# SPI_Bus_Transceiver.net
KiCad netlist of a schematic drawn in Altium Designer
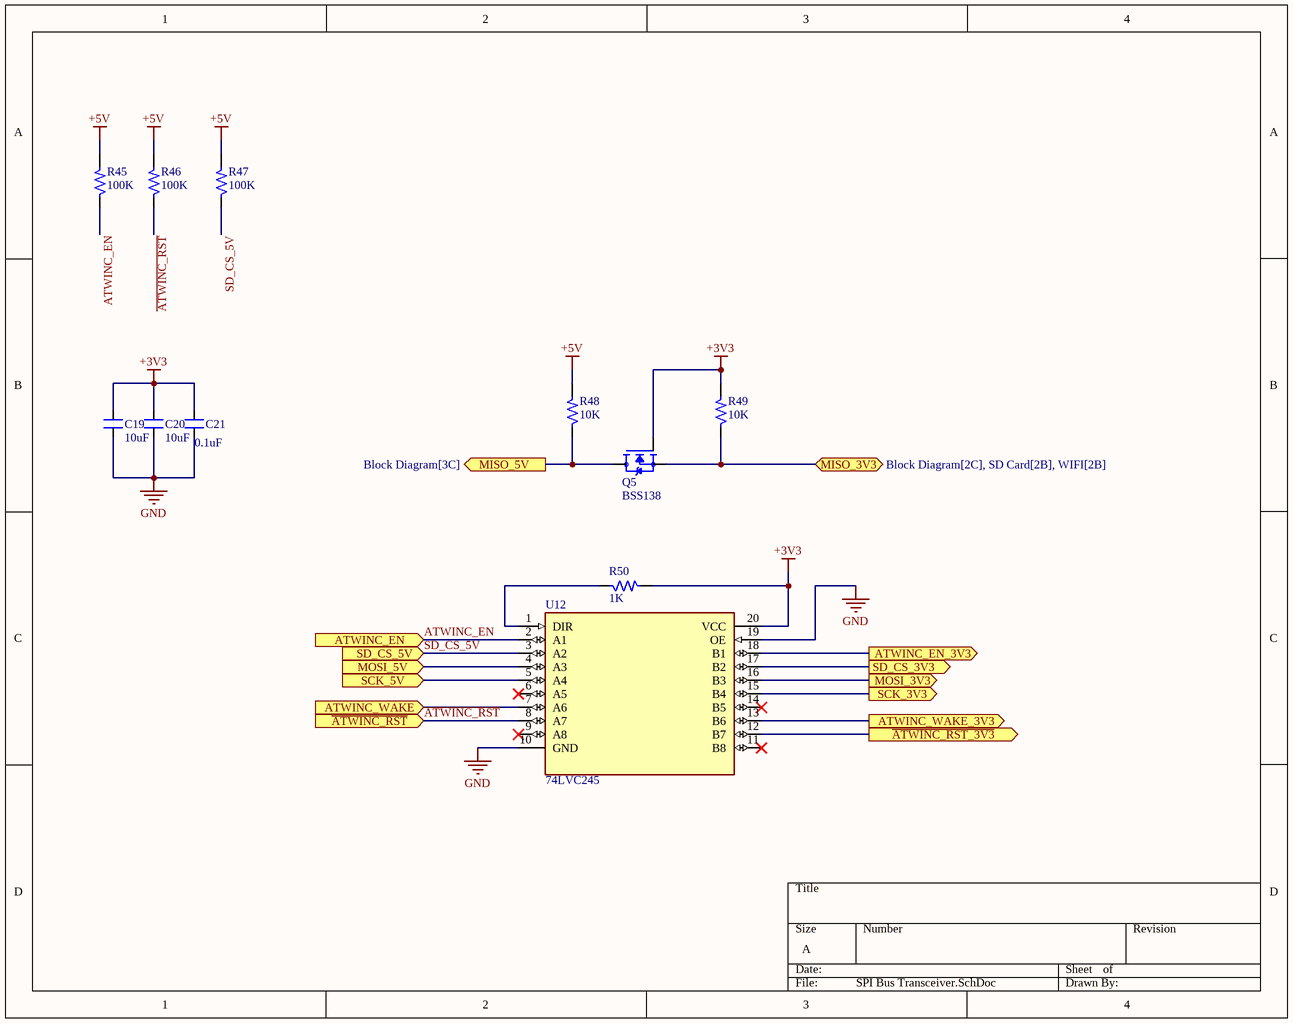
[diagram p0: SPI Bus Transceiver.SchDoc]

(export (version "E")
  (design (tool "Eeschema 10.0.6"))
  (components
    (comp (ref "C19")
      (value "10uF")
      (footprint "CAP_1206")
      (description "10µF ±10% 50V Ceramic Capacitor X7R 1206 (3216 Metric)")
      (fields
        (field (name "MANUFACTURER") "KEMET")
        (field (name "MANUFACTURER PART NUMBER") "CL31B106KBHNNNE")
      )
      (libsource (lib "ESTEEMPCBLIB") (part "CAP_10uF-50V-10%-1206"))
    )
    (comp (ref "C20")
      (value "10uF")
      (footprint "CAP_1206")
      (description "10µF ±10% 50V Ceramic Capacitor X7R 1206 (3216 Metric)")
      (fields
        (field (name "MANUFACTURER") "KEMET")
        (field (name "MANUFACTURER PART NUMBER") "CL31B106KBHNNNE")
      )
      (libsource (lib "ESTEEMPCBLIB") (part "CAP_10uF-50V-10%-1206"))
    )
    (comp (ref "C21")
      (value "0.1uF")
      (footprint "CAP_0805")
      (description "0.1µF ±5% 50V Ceramic Capacitor X7R 0805 (2012 Metric)")
      (fields
        (field (name "MANUFACTURER") "AVX Corporation")
        (field (name "MANUFACTURER PART NUMBER") "08055C104JAT4A")
      )
      (libsource (lib "ESTEEMPCBLIB") (part "CAP_0.1uF-50V-5%-0805"))
    )
    (comp (ref "Q5")
      (value "BSS138")
      (footprint "SOT95P240X111-3N")
      (description "N-Channel 50V 220mA (Ta) 360mW (Ta) Surface Mount SOT-23-3")
      (libsource (lib "TAREKPCBLIB") (part "BSS138"))
    )
    (comp (ref "R45")
      (value "100K")
      (footprint "RES_0805")
      (description "100 kOhms ±1% 0.125W, 1/8W Chip Resistor 0805 (2012 Metric) Automotive AEC-Q200 Thick Film")
      (fields (field (name "MANUFACTURER") "Walsin") (field (name "MANUFACTURER PART NUMBER") "WR08X1003FTL"))
      (libsource (lib "ESTEEMPCBLIB") (part "RES_100K-0.125W-1%-0805"))
    )
    (comp (ref "R46")
      (value "100K")
      (footprint "RES_0805")
      (description "100 kOhms ±1% 0.125W, 1/8W Chip Resistor 0805 (2012 Metric) Automotive AEC-Q200 Thick Film")
      (fields (field (name "MANUFACTURER") "Walsin") (field (name "MANUFACTURER PART NUMBER") "WR08X1003FTL"))
      (libsource (lib "ESTEEMPCBLIB") (part "RES_100K-0.125W-1%-0805"))
    )
    (comp (ref "R47")
      (value "100K")
      (footprint "RES_0805")
      (description "100 kOhms ±1% 0.125W, 1/8W Chip Resistor 0805 (2012 Metric) Automotive AEC-Q200 Thick Film")
      (fields (field (name "MANUFACTURER") "Walsin") (field (name "MANUFACTURER PART NUMBER") "WR08X1003FTL"))
      (libsource (lib "ESTEEMPCBLIB") (part "RES_100K-0.125W-1%-0805"))
    )
    (comp (ref "R48")
      (value "10K")
      (footprint "RES_0805")
      (description "10 kOhms ±1% 0.125W, 1/8W Chip Resistor 0805 (2012 Metric) Automotive AEC-Q200 Thick Film")
      (fields (field (name "MANUFACTURER") "CTS") (field (name "MANUFACTURER PART NUMBER") "WR08X1002FTL"))
      (libsource (lib "ESTEEMPCBLIB") (part "RES_10K-0.125W-1%-0805"))
    )
    (comp (ref "R49")
      (value "10K")
      (footprint "RES_0805")
      (description "10 kOhms ±1% 0.125W, 1/8W Chip Resistor 0805 (2012 Metric) Automotive AEC-Q200 Thick Film")
      (fields (field (name "MANUFACTURER") "CTS") (field (name "MANUFACTURER PART NUMBER") "WR08X1002FTL"))
      (libsource (lib "ESTEEMPCBLIB") (part "RES_10K-0.125W-1%-0805"))
    )
    (comp (ref "R50")
      (value "1K")
      (footprint "RES_0805")
      (description "1 kOhms ±1% 0.125W, 1/8W Chip Resistor 0805 (2012 Metric) Moisture Resistant Thick Film")
      (fields (field (name "MANUFACTURER") "Walsin") (field (name "MANUFACTURER PART NUMBER") "WR08X1001FTL"))
      (libsource (lib "ESTEEMPCBLIB") (part "RES_1K-0.125W-1%-0805"))
    )
    (comp (ref "U12")
      (value "74LVC245")
      (footprint "SOIC-20-W")
      (description "Transceiver, Non-Inverting 1 Element 8 Bit per Element 3-State Output 20-TSSOP")
      (fields (field (name "MF") "ON Semiconductor"))
      (libsource (lib "TAREKPCBLIB") (part "74LVC245"))
    )
  )
  (nets
    (net (code "1") (name "+3V3") (class "Default")
      (node (ref "C19") (pin "2") (pinfunction "2_2") (pintype "passive"))
      (node (ref "C20") (pin "2") (pinfunction "2_2") (pintype "passive"))
      (node (ref "C21") (pin "2") (pinfunction "2_2") (pintype "passive"))
      (node (ref "Q5") (pin "1") (pinfunction "G_1") (pintype "passive"))
      (node (ref "R49") (pin "2") (pinfunction "2_2") (pintype "passive"))
      (node (ref "R50") (pin "2") (pinfunction "2_2") (pintype "passive"))
      (node (ref "U12") (pin "20") (pinfunction "VCC_20") (pintype "power_in"))
    )
    (net (code "2") (name "+5V") (class "Default")
      (node (ref "R45") (pin "2") (pinfunction "2_2") (pintype "passive"))
      (node (ref "R46") (pin "2") (pinfunction "2_2") (pintype "passive"))
      (node (ref "R47") (pin "2") (pinfunction "2_2") (pintype "passive"))
      (node (ref "R48") (pin "2") (pinfunction "2_2") (pintype "passive"))
    )
    (net (code "3") (name "/ATWINC_EN") (class "Default")
      (node (ref "R45") (pin "1") (pinfunction "1_1") (pintype "passive"))
      (node (ref "U12") (pin "2") (pinfunction "A1_2") (pintype "bidirectional"))
    )
    (net (code "4") (name "/ATWINC_EN_3V3") (class "Default")
      (node (ref "U12") (pin "18") (pinfunction "B1_18") (pintype "bidirectional"))
    )
    (net (code "5") (name "/ATWINC_RST") (class "Default")
      (node (ref "R46") (pin "1") (pinfunction "1_1") (pintype "passive"))
      (node (ref "U12") (pin "8") (pinfunction "A7_8") (pintype "bidirectional"))
    )
    (net (code "6") (name "/ATWINC_RST_3V3") (class "Default")
      (node (ref "U12") (pin "12") (pinfunction "B7_12") (pintype "bidirectional"))
    )
    (net (code "7") (name "/ATWINC_WAKE") (class "Default")
      (node (ref "U12") (pin "7") (pinfunction "A6_7") (pintype "bidirectional"))
    )
    (net (code "8") (name "/ATWINC_WAKE_3V3") (class "Default")
      (node (ref "U12") (pin "13") (pinfunction "B6_13") (pintype "bidirectional"))
    )
    (net (code "9") (name "/MISO_3V3") (class "Default")
      (node (ref "Q5") (pin "2") (pinfunction "S_2") (pintype "passive"))
      (node (ref "R49") (pin "1") (pinfunction "1_1") (pintype "passive"))
    )
    (net (code "10") (name "/MISO_5V") (class "Default")
      (node (ref "Q5") (pin "3") (pinfunction "D_3") (pintype "passive"))
      (node (ref "R48") (pin "1") (pinfunction "1_1") (pintype "passive"))
    )
    (net (code "11") (name "/MOSI_3V3") (class "Default")
      (node (ref "U12") (pin "16") (pinfunction "B3_16") (pintype "bidirectional"))
    )
    (net (code "12") (name "/MOSI_5V") (class "Default")
      (node (ref "U12") (pin "4") (pinfunction "A3_4") (pintype "bidirectional"))
    )
    (net (code "13") (name "/SCK_3V3") (class "Default")
      (node (ref "U12") (pin "15") (pinfunction "B4_15") (pintype "bidirectional"))
    )
    (net (code "14") (name "/SCK_5V") (class "Default")
      (node (ref "U12") (pin "5") (pinfunction "A4_5") (pintype "bidirectional"))
    )
    (net (code "15") (name "/SD_CS_3V3") (class "Default")
      (node (ref "U12") (pin "17") (pinfunction "B2_17") (pintype "bidirectional"))
    )
    (net (code "16") (name "/SD_CS_5V") (class "Default")
      (node (ref "R47") (pin "1") (pinfunction "1_1") (pintype "passive"))
      (node (ref "U12") (pin "3") (pinfunction "A2_3") (pintype "bidirectional"))
    )
    (net (code "17") (name "GND") (class "Default")
      (node (ref "C19") (pin "1") (pinfunction "1_1") (pintype "passive"))
      (node (ref "C20") (pin "1") (pinfunction "1_1") (pintype "passive"))
      (node (ref "C21") (pin "1") (pinfunction "1_1") (pintype "passive"))
      (node (ref "U12") (pin "10") (pinfunction "GND_10") (pintype "power_in"))
      (node (ref "U12") (pin "19") (pinfunction "OE_19") (pintype "input"))
    )
    (net (code "18") (name "Net-(U12-DIR)") (class "Default")
      (node (ref "R50") (pin "1") (pinfunction "1_1") (pintype "passive"))
      (node (ref "U12") (pin "1") (pinfunction "DIR_1") (pintype "input"))
    )
    (net (code "19") (name "unconnected-(U12-A5-Pad6)") (class "Default")
      (node (ref "U12") (pin "6") (pinfunction "A5_6") (pintype "bidirectional+no_connect"))
    )
    (net (code "20") (name "unconnected-(U12-A8-Pad9)") (class "Default")
      (node (ref "U12") (pin "9") (pinfunction "A8_9") (pintype "bidirectional+no_connect"))
    )
    (net (code "21") (name "unconnected-(U12-B5-Pad14)") (class "Default")
      (node (ref "U12") (pin "14") (pinfunction "B5_14") (pintype "bidirectional+no_connect"))
    )
    (net (code "22") (name "unconnected-(U12-B8-Pad11)") (class "Default")
      (node (ref "U12") (pin "11") (pinfunction "B8_11") (pintype "bidirectional+no_connect"))
    )
  )
)
